# CHRT.net
KiCad netlist of a schematic drawn in Altium Designer
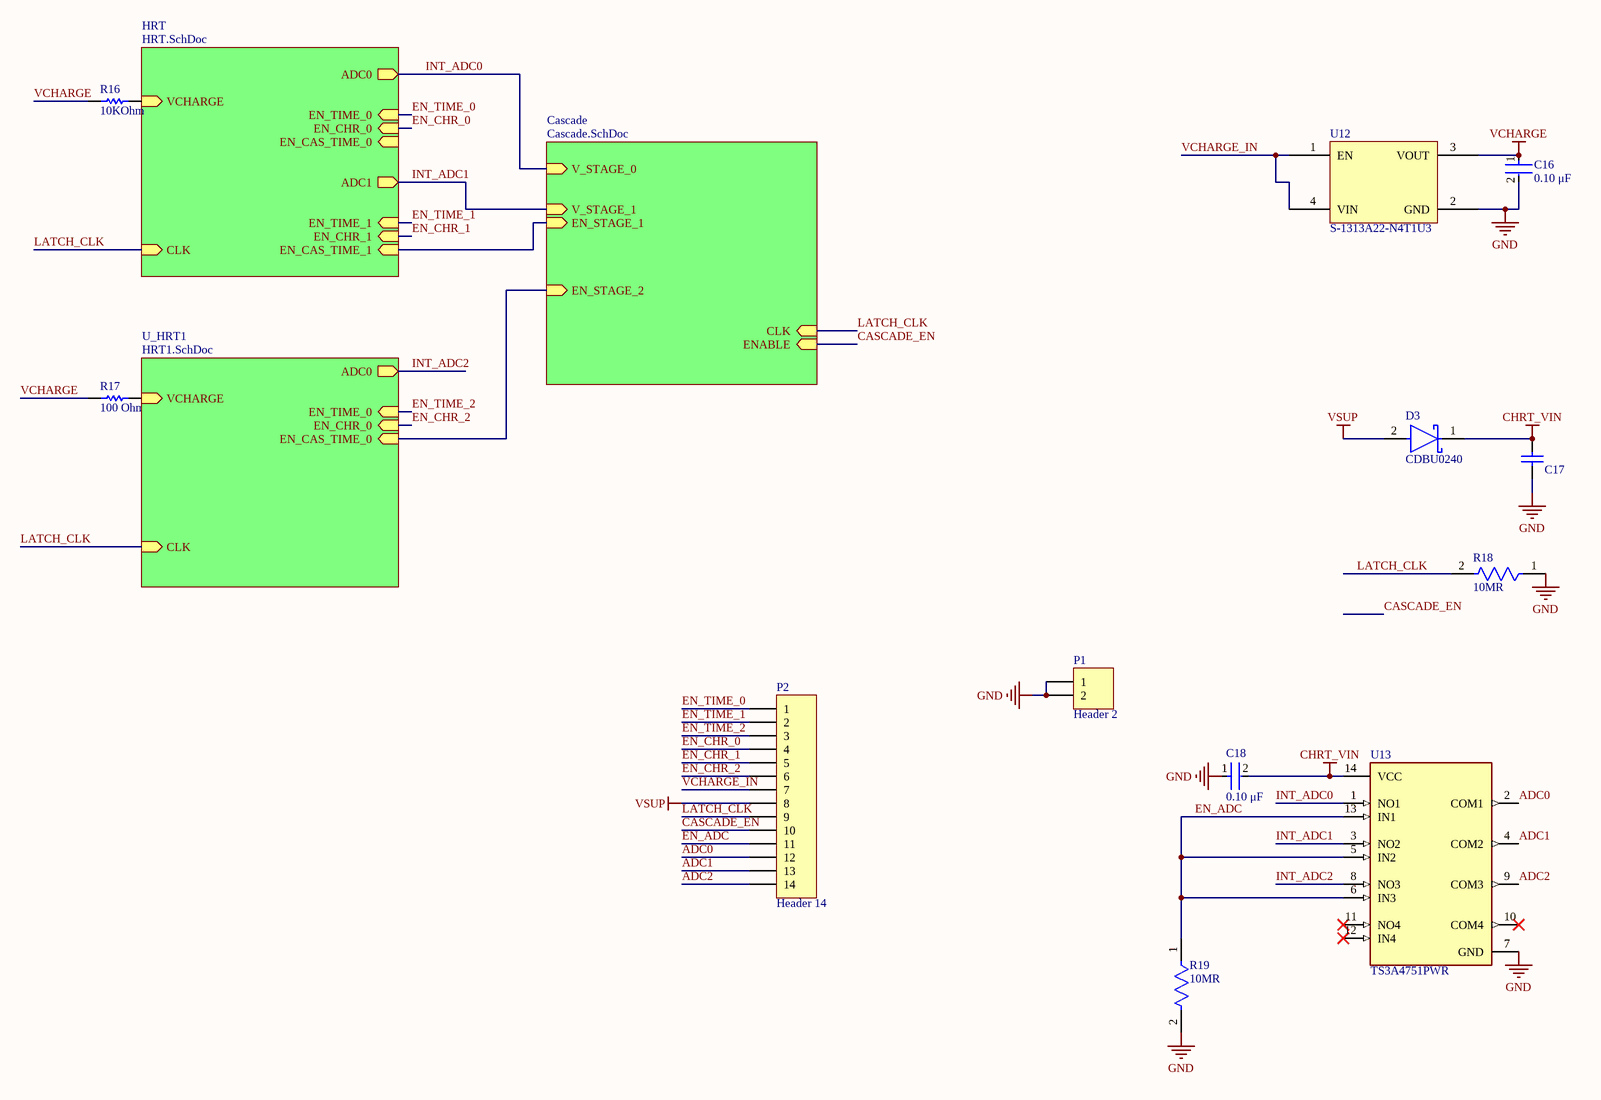
[diagram p0: CHRT.SchDoc]

(export (version "E")
  (design (tool "Eeschema 10.0.6"))
  (components
    (comp (ref "C16")
      (value "C0402C104K8PACTU")
      (footprint "FP-C0402-BB-MFG")
      (description "CAP CER 0.1UF 10V X5R 0402")
      (fields
        (field (name "CAPACITANCE") "0.10 μF")
        (field (name "MANUFACTURER") "Kemet")
        (field (name "TOLERANCE") "0.1")
      )
      (libsource (lib "Altium Content Vault") (part "b4654b650e69147ec39a6b967a45e02"))
    )
    (comp (ref "C17")
      (value "ZRB15XR61A106ME01D")
      (footprint "CAPC1005X55X25NL05T10")
      (fields (field (name "MANUFACTURER") "Murata") (field (name "PART NUMBER") "GRM155R60G106ME44D"))
      (libsource (lib "Altium Content Vault") (part "CAP"))
    )
    (comp (ref "C18")
      (value "C0402C104K8PACTU")
      (footprint "FP-C0402-BB-MFG")
      (description "CAP CER 0.1UF 10V X5R 0402")
      (fields
        (field (name "CAPACITANCE") "0.10 μF")
        (field (name "MANUFACTURER") "Kemet")
        (field (name "TOLERANCE") "0.1")
      )
      (libsource (lib "Altium Content Vault") (part "b4654b650e69147ec39a6b967a45e02"))
    )
    (comp (ref "D3")
      (value "CDBU0240")
      (footprint "FP-SOD-523F-MFG")
      (description "DIODE SCHOTTKY 40V 200MA 0603")
      (libsource (lib "Altium Content Vault") (part "1d6ec82d83fb6aee721767c19dac4b9"))
    )
    (comp (ref "P1")
      (value "Header 2")
      (footprint "HDR1X2")
      (description "Header, 2-Pin")
      (fields (field (name "PUBLISHER") "Altium Limited"))
      (libsource (lib "Miscellaneous Connectors") (part "Header 2"))
    )
    (comp (ref "P2")
      (value "Header 14")
      (footprint "HDR1X14")
      (description "Header, 14-Pin")
      (fields (field (name "PUBLISHER") "Altium Limited"))
      (libsource (lib "Miscellaneous Connectors") (part "Header 14"))
    )
    (comp (ref "R16")
      (value "RMCF0402FT10K0")
      (footprint "RESC1005X40X25LL05T05")
      (description "Chip Resistor, 10 KOhm, +/- 1%, 0.1 W, -55 to 155 degC, 0402 (1005 Metric), RoHS, Tape and Reel")
      (fields
        (field (name "RESISTANCE") "10KOhm")
        (field (name "TOLERANCE") "1%")
        (field (name "MANUFACTURER") "Panasonic")
      )
      (libsource (lib "Altium Content Vault") (part "RES-2"))
    )
    (comp (ref "R17")
      (value "ERJ-2RKF1000X")
      (footprint "RESC1005X40X25LL05T05")
      (description "Chip Resistor, 100 Ohm, +/- 1%, 100 mW, -55 to 155 degC, 0402 (1005 Metric), RoHS, Tape and Reel")
      (fields
        (field (name "MANUFACTURER") "Basic Passives")
        (field (name "TOLERANCE") "1%")
        (field (name "RESISTANCE") "100 Ohm")
      )
      (libsource (lib "Altium Content Vault") (part "RES-2"))
    )
    (comp (ref "R18")
      (value "CRCW040210M0JNED")
      (footprint "FP-CRCW0402-e3-IPC_C")
      (description "RES Thick Film, 10MΩ, 5%, 0.063W, 200ppm/°C, 0402")
      (fields (field (name "TOLERANCE") "5%") (field (name "RESISTANCE") "10MR"))
      (libsource (lib "Altium Content Vault") (part "1029c3af85768c4190bb7ad29bc67b5"))
    )
    (comp (ref "R19")
      (value "CRCW040210M0JNED")
      (footprint "FP-CRCW0402-e3-IPC_C")
      (description "RES Thick Film, 10MΩ, 5%, 0.063W, 200ppm/°C, 0402")
      (fields (field (name "TOLERANCE") "5%") (field (name "RESISTANCE") "10MR"))
      (libsource (lib "Altium Content Vault") (part "1029c3af85768c4190bb7ad29bc67b5"))
    )
    (comp (ref "U12")
      (value "S-1313A22-N4T1U3")
      (footprint "SC82AB")
      (libsource (lib "Integrated_Library1") (part "S-1313A22-N4T1U3"))
    )
    (comp (ref "U13")
      (value "TS3A4751PWR")
      (footprint "FP-PW0014A-IPC_C")
      (description "IC SWITCH QUAD SPST 14TSSOP")
      (libsource (lib "Altium Content Vault") (part "75fdcfb842d41a92b92a478e82e68ae"))
    )
  )
  (nets
    (net (code "2") (name "/ADC0") (class "Default")
      (node (ref "P2") (pin "12") (pinfunction "12_12") (pintype "passive"))
      (node (ref "U13") (pin "2") (pinfunction "COM1_2") (pintype "output"))
    )
    (net (code "3") (name "/ADC1") (class "Default")
      (node (ref "P2") (pin "13") (pinfunction "13_13") (pintype "passive"))
      (node (ref "U13") (pin "4") (pinfunction "COM2_4") (pintype "output"))
    )
    (net (code "4") (name "/ADC2") (class "Default")
      (node (ref "P2") (pin "14") (pinfunction "14_14") (pintype "passive"))
      (node (ref "U13") (pin "9") (pinfunction "COM3_9") (pintype "output"))
    )
    (net (code "5") (name "/CASCADE_EN") (class "Default")
      (node (ref "P2") (pin "10") (pinfunction "10_10") (pintype "passive"))
    )
    (net (code "6") (name "/EN_ADC") (class "Default")
      (node (ref "P2") (pin "11") (pinfunction "11_11") (pintype "passive"))
      (node (ref "R19") (pin "1") (pinfunction "1_1") (pintype "passive"))
      (node (ref "U13") (pin "13") (pinfunction "IN1_13") (pintype "input"))
      (node (ref "U13") (pin "5") (pinfunction "IN2_5") (pintype "input"))
      (node (ref "U13") (pin "6") (pinfunction "IN3_6") (pintype "input"))
    )
    (net (code "10") (name "/EN_CHR_0") (class "Default")
      (node (ref "P2") (pin "4") (pinfunction "4_4") (pintype "passive"))
    )
    (net (code "11") (name "/EN_CHR_1") (class "Default")
      (node (ref "P2") (pin "5") (pinfunction "5_5") (pintype "passive"))
    )
    (net (code "12") (name "/EN_CHR_2") (class "Default")
      (node (ref "P2") (pin "6") (pinfunction "6_6") (pintype "passive"))
    )
    (net (code "13") (name "/EN_TIME_0") (class "Default")
      (node (ref "P2") (pin "1") (pinfunction "1_1") (pintype "passive"))
    )
    (net (code "14") (name "/EN_TIME_1") (class "Default")
      (node (ref "P2") (pin "2") (pinfunction "2_2") (pintype "passive"))
    )
    (net (code "15") (name "/EN_TIME_2") (class "Default")
      (node (ref "P2") (pin "3") (pinfunction "3_3") (pintype "passive"))
    )
    (net (code "16") (name "/INT_ADC0") (class "Default")
      (node (ref "U13") (pin "1") (pinfunction "NO1_1") (pintype "input"))
    )
    (net (code "17") (name "/INT_ADC1") (class "Default")
      (node (ref "U13") (pin "3") (pinfunction "NO2_3") (pintype "input"))
    )
    (net (code "18") (name "/INT_ADC2") (class "Default")
      (node (ref "U13") (pin "8") (pinfunction "NO3_8") (pintype "input"))
    )
    (net (code "19") (name "/LATCH_CLK") (class "Default")
      (node (ref "P2") (pin "9") (pinfunction "9_9") (pintype "passive"))
      (node (ref "R18") (pin "2") (pinfunction "2_2") (pintype "passive"))
    )
    (net (code "20") (name "/VCHARGE_1") (class "Default")
      (node (ref "R17") (pin "2") (pinfunction "2_2") (pintype "passive"))
    )
    (net (code "21") (name "/VCHARGE_2") (class "Default")
      (node (ref "R16") (pin "2") (pinfunction "2_2") (pintype "passive"))
    )
    (net (code "22") (name "/VCHARGE_IN") (class "Default")
      (node (ref "P2") (pin "7") (pinfunction "7_7") (pintype "passive"))
      (node (ref "U12") (pin "1") (pinfunction "EN_1") (pintype "passive"))
      (node (ref "U12") (pin "4") (pinfunction "VIN_4") (pintype "passive"))
    )
    (net (code "23") (name "CHRT_VIN") (class "Default")
      (node (ref "C17") (pin "2") (pinfunction "2_2") (pintype "passive"))
      (node (ref "C18") (pin "2") (pinfunction "2_2") (pintype "passive"))
      (node (ref "D3") (pin "1") (pinfunction "C_1") (pintype "passive"))
      (node (ref "U13") (pin "14") (pinfunction "VCC_14") (pintype "power_in"))
    )
    (net (code "24") (name "GND") (class "Default")
      (node (ref "C16") (pin "2") (pinfunction "2_2") (pintype "passive"))
      (node (ref "C17") (pin "1") (pinfunction "1_1") (pintype "passive"))
      (node (ref "C18") (pin "1") (pinfunction "1_1") (pintype "passive"))
      (node (ref "P1") (pin "1") (pinfunction "1_1") (pintype "passive"))
      (node (ref "P1") (pin "2") (pinfunction "2_2") (pintype "passive"))
      (node (ref "R18") (pin "1") (pinfunction "1_1") (pintype "passive"))
      (node (ref "R19") (pin "2") (pinfunction "2_2") (pintype "passive"))
      (node (ref "U12") (pin "2") (pinfunction "GND_2") (pintype "passive"))
      (node (ref "U13") (pin "7") (pinfunction "GND_7") (pintype "power_in"))
    )
    (net (code "25") (name "VCHARGE") (class "Default")
      (node (ref "C16") (pin "1") (pinfunction "1_1") (pintype "passive"))
      (node (ref "R16") (pin "1") (pinfunction "1_1") (pintype "passive"))
      (node (ref "R17") (pin "1") (pinfunction "1_1") (pintype "passive"))
      (node (ref "U12") (pin "3") (pinfunction "VOUT_3") (pintype "passive"))
    )
    (net (code "26") (name "VSUP") (class "Default")
      (node (ref "D3") (pin "2") (pinfunction "A_2") (pintype "passive"))
      (node (ref "P2") (pin "8") (pinfunction "8_8") (pintype "passive"))
    )
    (net (code "27") (name "unconnected-(U13-COM4-Pad10)") (class "Default")
      (node (ref "U13") (pin "10") (pinfunction "COM4_10") (pintype "output+no_connect"))
    )
    (net (code "28") (name "unconnected-(U13-IN4-Pad12)") (class "Default")
      (node (ref "U13") (pin "12") (pinfunction "IN4_12") (pintype "input+no_connect"))
    )
    (net (code "29") (name "unconnected-(U13-NO4-Pad11)") (class "Default")
      (node (ref "U13") (pin "11") (pinfunction "NO4_11") (pintype "input+no_connect"))
    )
  )
)
